# scb-with-pour-revision-final.net
KiCad netlist of a schematic drawn in EAGLE
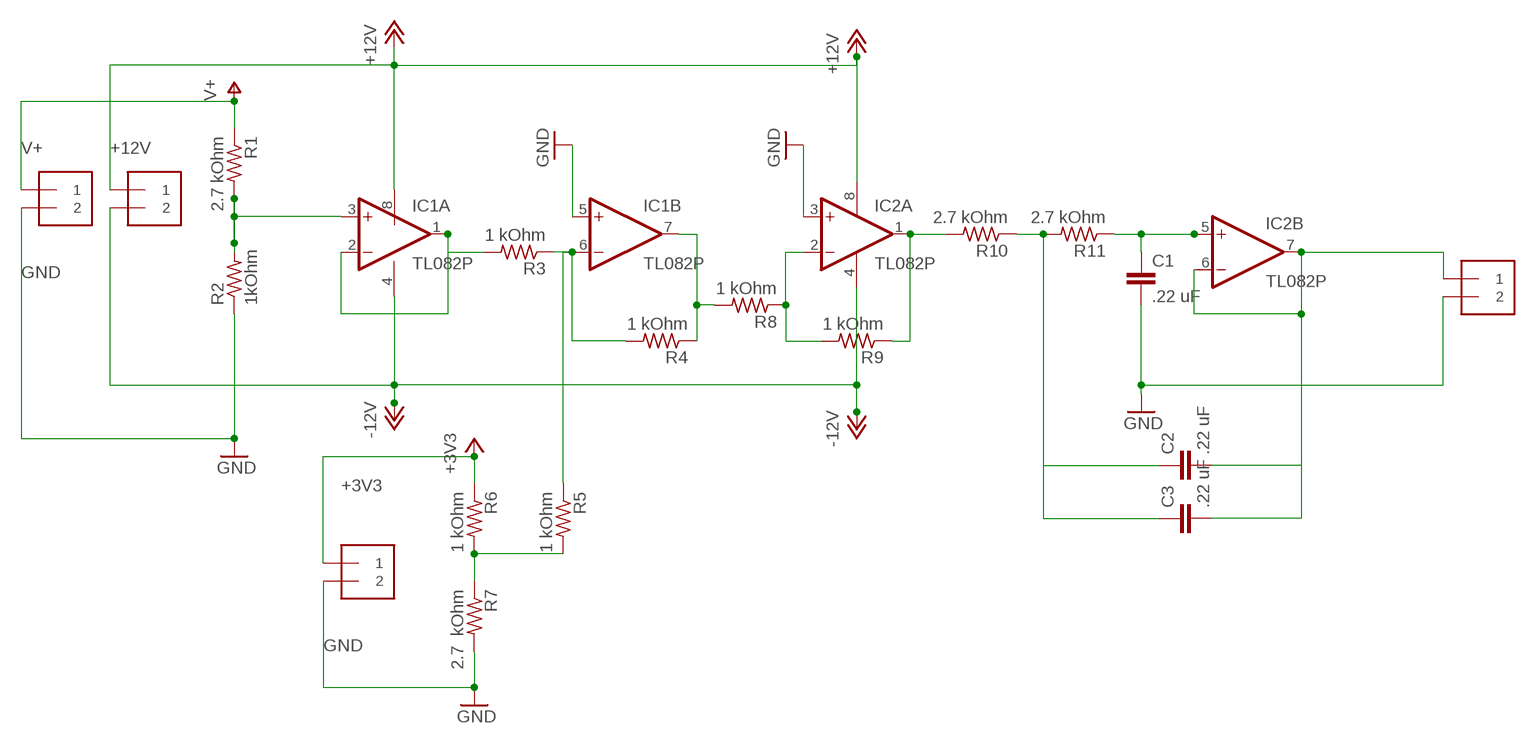
[diagram p0: schematic, sheet 1]

(export (version "E")
  (design (tool "Eeschema 10.0.6"))
  (components
    (comp (ref "C1")
      (value ".22 uF")
      (footprint "eagle-import:C5B5")
      (libsource (lib "eagle-import") (part "C5/5"))
    )
    (comp (ref "C2")
      (value ".22 uF")
      (footprint "eagle-import:C5B5")
      (libsource (lib "eagle-import") (part "C5/5"))
    )
    (comp (ref "C3")
      (value ".22 uF")
      (footprint "eagle-import:C5B5")
      (libsource (lib "eagle-import") (part "C5/5"))
    )
    (comp (ref "IC1")
      (value "TL082P")
      (footprint "eagle-import:DIL08")
      (libsource (lib "eagle-import") (part "TL082P"))
    )
    (comp (ref "IC2")
      (value "TL082P")
      (footprint "eagle-import:DIL08")
      (libsource (lib "eagle-import") (part "TL082P"))
    )
    (comp (ref "J1")
      (value "1X2-3.5MM")
      (footprint "eagle-import:3.5MMTERM")
      (libsource (lib "eagle-import") (part "1X2-3.5MM"))
    )
    (comp (ref "J2")
      (value "1X2-3.5MM")
      (footprint "eagle-import:3.5MMTERM")
      (libsource (lib "eagle-import") (part "1X2-3.5MM"))
    )
    (comp (ref "J3")
      (value "1X2-3.5MM")
      (footprint "eagle-import:3.5MMTERM")
      (libsource (lib "eagle-import") (part "1X2-3.5MM"))
    )
    (comp (ref "J4")
      (value "1X2-3.5MM")
      (footprint "eagle-import:3.5MMTERM")
      (libsource (lib "eagle-import") (part "1X2-3.5MM"))
    )
    (comp (ref "R1")
      (value "2.7 kOhm")
      (footprint "eagle-import:0207_10")
      (libsource (lib "eagle-import") (part "R-US_0207/10"))
    )
    (comp (ref "R2")
      (value "1kOhm")
      (footprint "eagle-import:0207_10")
      (libsource (lib "eagle-import") (part "R-US_0207/10"))
    )
    (comp (ref "R3")
      (value "1 kOhm")
      (footprint "eagle-import:0207_10")
      (libsource (lib "eagle-import") (part "R-US_0207/10"))
    )
    (comp (ref "R4")
      (value "1 kOhm")
      (footprint "eagle-import:0207_10")
      (libsource (lib "eagle-import") (part "R-US_0207/10"))
    )
    (comp (ref "R5")
      (value "1 kOhm")
      (footprint "eagle-import:0207_10")
      (libsource (lib "eagle-import") (part "R-US_0207/10"))
    )
    (comp (ref "R6")
      (value "1 kOhm")
      (footprint "eagle-import:0207_10")
      (libsource (lib "eagle-import") (part "R-US_0207/10"))
    )
    (comp (ref "R7")
      (value "2.7 kOhm")
      (footprint "eagle-import:0207_10")
      (libsource (lib "eagle-import") (part "R-US_0207/10"))
    )
    (comp (ref "R8")
      (value "1 kOhm")
      (footprint "eagle-import:0207_10")
      (libsource (lib "eagle-import") (part "R-US_0207/10"))
    )
    (comp (ref "R9")
      (value "1 kOhm")
      (footprint "eagle-import:0207_10")
      (libsource (lib "eagle-import") (part "R-US_0207/10"))
    )
    (comp (ref "R10")
      (value "2.7 kOhm")
      (footprint "eagle-import:0207_10")
      (libsource (lib "eagle-import") (part "R-US_0207/10"))
    )
    (comp (ref "R11")
      (value "2.7 kOhm")
      (footprint "eagle-import:0207_10")
      (libsource (lib "eagle-import") (part "R-US_0207/10"))
    )
  )
  (nets
    (net (code "1") (name "+3V3") (class "Default")
      (node (ref "J2") (pin "1") (pinfunction "1_1") (pintype "passive"))
      (node (ref "R6") (pin "1") (pinfunction "1_1") (pintype "passive"))
    )
    (net (code "2") (name "+12V") (class "Default")
      (node (ref "IC1") (pin "8") (pinfunction "V+_8") (pintype "power_in"))
      (node (ref "IC2") (pin "8") (pinfunction "V+_8") (pintype "power_in"))
      (node (ref "J1") (pin "1") (pinfunction "1_1") (pintype "passive"))
    )
    (net (code "3") (name "-12V") (class "Default")
      (node (ref "IC1") (pin "4") (pinfunction "V-_4") (pintype "power_in"))
      (node (ref "IC2") (pin "4") (pinfunction "V-_4") (pintype "power_in"))
      (node (ref "J1") (pin "2") (pinfunction "2_2") (pintype "passive"))
    )
    (net (code "4") (name "GND") (class "Default")
      (node (ref "C1") (pin "2") (pinfunction "2_2") (pintype "passive"))
      (node (ref "IC1") (pin "5") (pinfunction "+IN_5") (pintype "input"))
      (node (ref "IC2") (pin "3") (pinfunction "+IN_3") (pintype "input"))
      (node (ref "J2") (pin "2") (pinfunction "2_2") (pintype "passive"))
      (node (ref "J3") (pin "2") (pinfunction "2_2") (pintype "passive"))
      (node (ref "J4") (pin "2") (pinfunction "2_2") (pintype "passive"))
      (node (ref "R2") (pin "1") (pinfunction "1_1") (pintype "passive"))
      (node (ref "R7") (pin "2") (pinfunction "2_2") (pintype "passive"))
    )
    (net (code "5") (name "Net-(C2-Pad1)") (class "Default")
      (node (ref "C2") (pin "1") (pinfunction "1_1") (pintype "passive"))
      (node (ref "C3") (pin "1") (pinfunction "1_1") (pintype "passive"))
      (node (ref "R10") (pin "1") (pinfunction "1_1") (pintype "passive"))
      (node (ref "R11") (pin "2") (pinfunction "2_2") (pintype "passive"))
    )
    (net (code "6") (name "Net-(IC1A-+IN)") (class "Default")
      (node (ref "IC1") (pin "3") (pinfunction "+IN_3") (pintype "input"))
      (node (ref "R1") (pin "2") (pinfunction "2_2") (pintype "passive"))
      (node (ref "R2") (pin "2") (pinfunction "2_2") (pintype "passive"))
    )
    (net (code "7") (name "Net-(IC1A--IN)") (class "Default")
      (node (ref "IC1") (pin "1") (pinfunction "OUT_1") (pintype "output"))
      (node (ref "IC1") (pin "2") (pinfunction "-IN_2") (pintype "input"))
      (node (ref "R3") (pin "2") (pinfunction "2_2") (pintype "passive"))
    )
    (net (code "8") (name "Net-(IC1B--IN)") (class "Default")
      (node (ref "IC1") (pin "6") (pinfunction "-IN_6") (pintype "input"))
      (node (ref "R3") (pin "1") (pinfunction "1_1") (pintype "passive"))
      (node (ref "R4") (pin "2") (pinfunction "2_2") (pintype "passive"))
      (node (ref "R5") (pin "1") (pinfunction "1_1") (pintype "passive"))
    )
    (net (code "9") (name "Net-(IC1B-OUT)") (class "Default")
      (node (ref "IC1") (pin "7") (pinfunction "OUT_7") (pintype "output"))
      (node (ref "R4") (pin "1") (pinfunction "1_1") (pintype "passive"))
      (node (ref "R8") (pin "2") (pinfunction "2_2") (pintype "passive"))
    )
    (net (code "10") (name "Net-(IC2A--IN)") (class "Default")
      (node (ref "IC2") (pin "2") (pinfunction "-IN_2") (pintype "input"))
      (node (ref "R8") (pin "1") (pinfunction "1_1") (pintype "passive"))
      (node (ref "R9") (pin "2") (pinfunction "2_2") (pintype "passive"))
    )
    (net (code "11") (name "Net-(IC2A-OUT)") (class "Default")
      (node (ref "IC2") (pin "1") (pinfunction "OUT_1") (pintype "output"))
      (node (ref "R10") (pin "2") (pinfunction "2_2") (pintype "passive"))
      (node (ref "R9") (pin "1") (pinfunction "1_1") (pintype "passive"))
    )
    (net (code "12") (name "Net-(IC2B-+IN)") (class "Default")
      (node (ref "C1") (pin "1") (pinfunction "1_1") (pintype "passive"))
      (node (ref "IC2") (pin "5") (pinfunction "+IN_5") (pintype "input"))
      (node (ref "R11") (pin "1") (pinfunction "1_1") (pintype "passive"))
    )
    (net (code "13") (name "Net-(IC2B--IN)") (class "Default")
      (node (ref "C2") (pin "2") (pinfunction "2_2") (pintype "passive"))
      (node (ref "C3") (pin "2") (pinfunction "2_2") (pintype "passive"))
      (node (ref "IC2") (pin "6") (pinfunction "-IN_6") (pintype "input"))
      (node (ref "IC2") (pin "7") (pinfunction "OUT_7") (pintype "output"))
      (node (ref "J4") (pin "1") (pinfunction "1_1") (pintype "passive"))
    )
    (net (code "14") (name "Net-(R5-Pad2)") (class "Default")
      (node (ref "R5") (pin "2") (pinfunction "2_2") (pintype "passive"))
      (node (ref "R6") (pin "2") (pinfunction "2_2") (pintype "passive"))
      (node (ref "R7") (pin "1") (pinfunction "1_1") (pintype "passive"))
    )
    (net (code "15") (name "V+") (class "Default")
      (node (ref "J3") (pin "1") (pinfunction "1_1") (pintype "passive"))
      (node (ref "R1") (pin "1") (pinfunction "1_1") (pintype "passive"))
    )
  )
)
